# zloshnikrev1.net
KiCad netlist of a schematic drawn in EAGLE
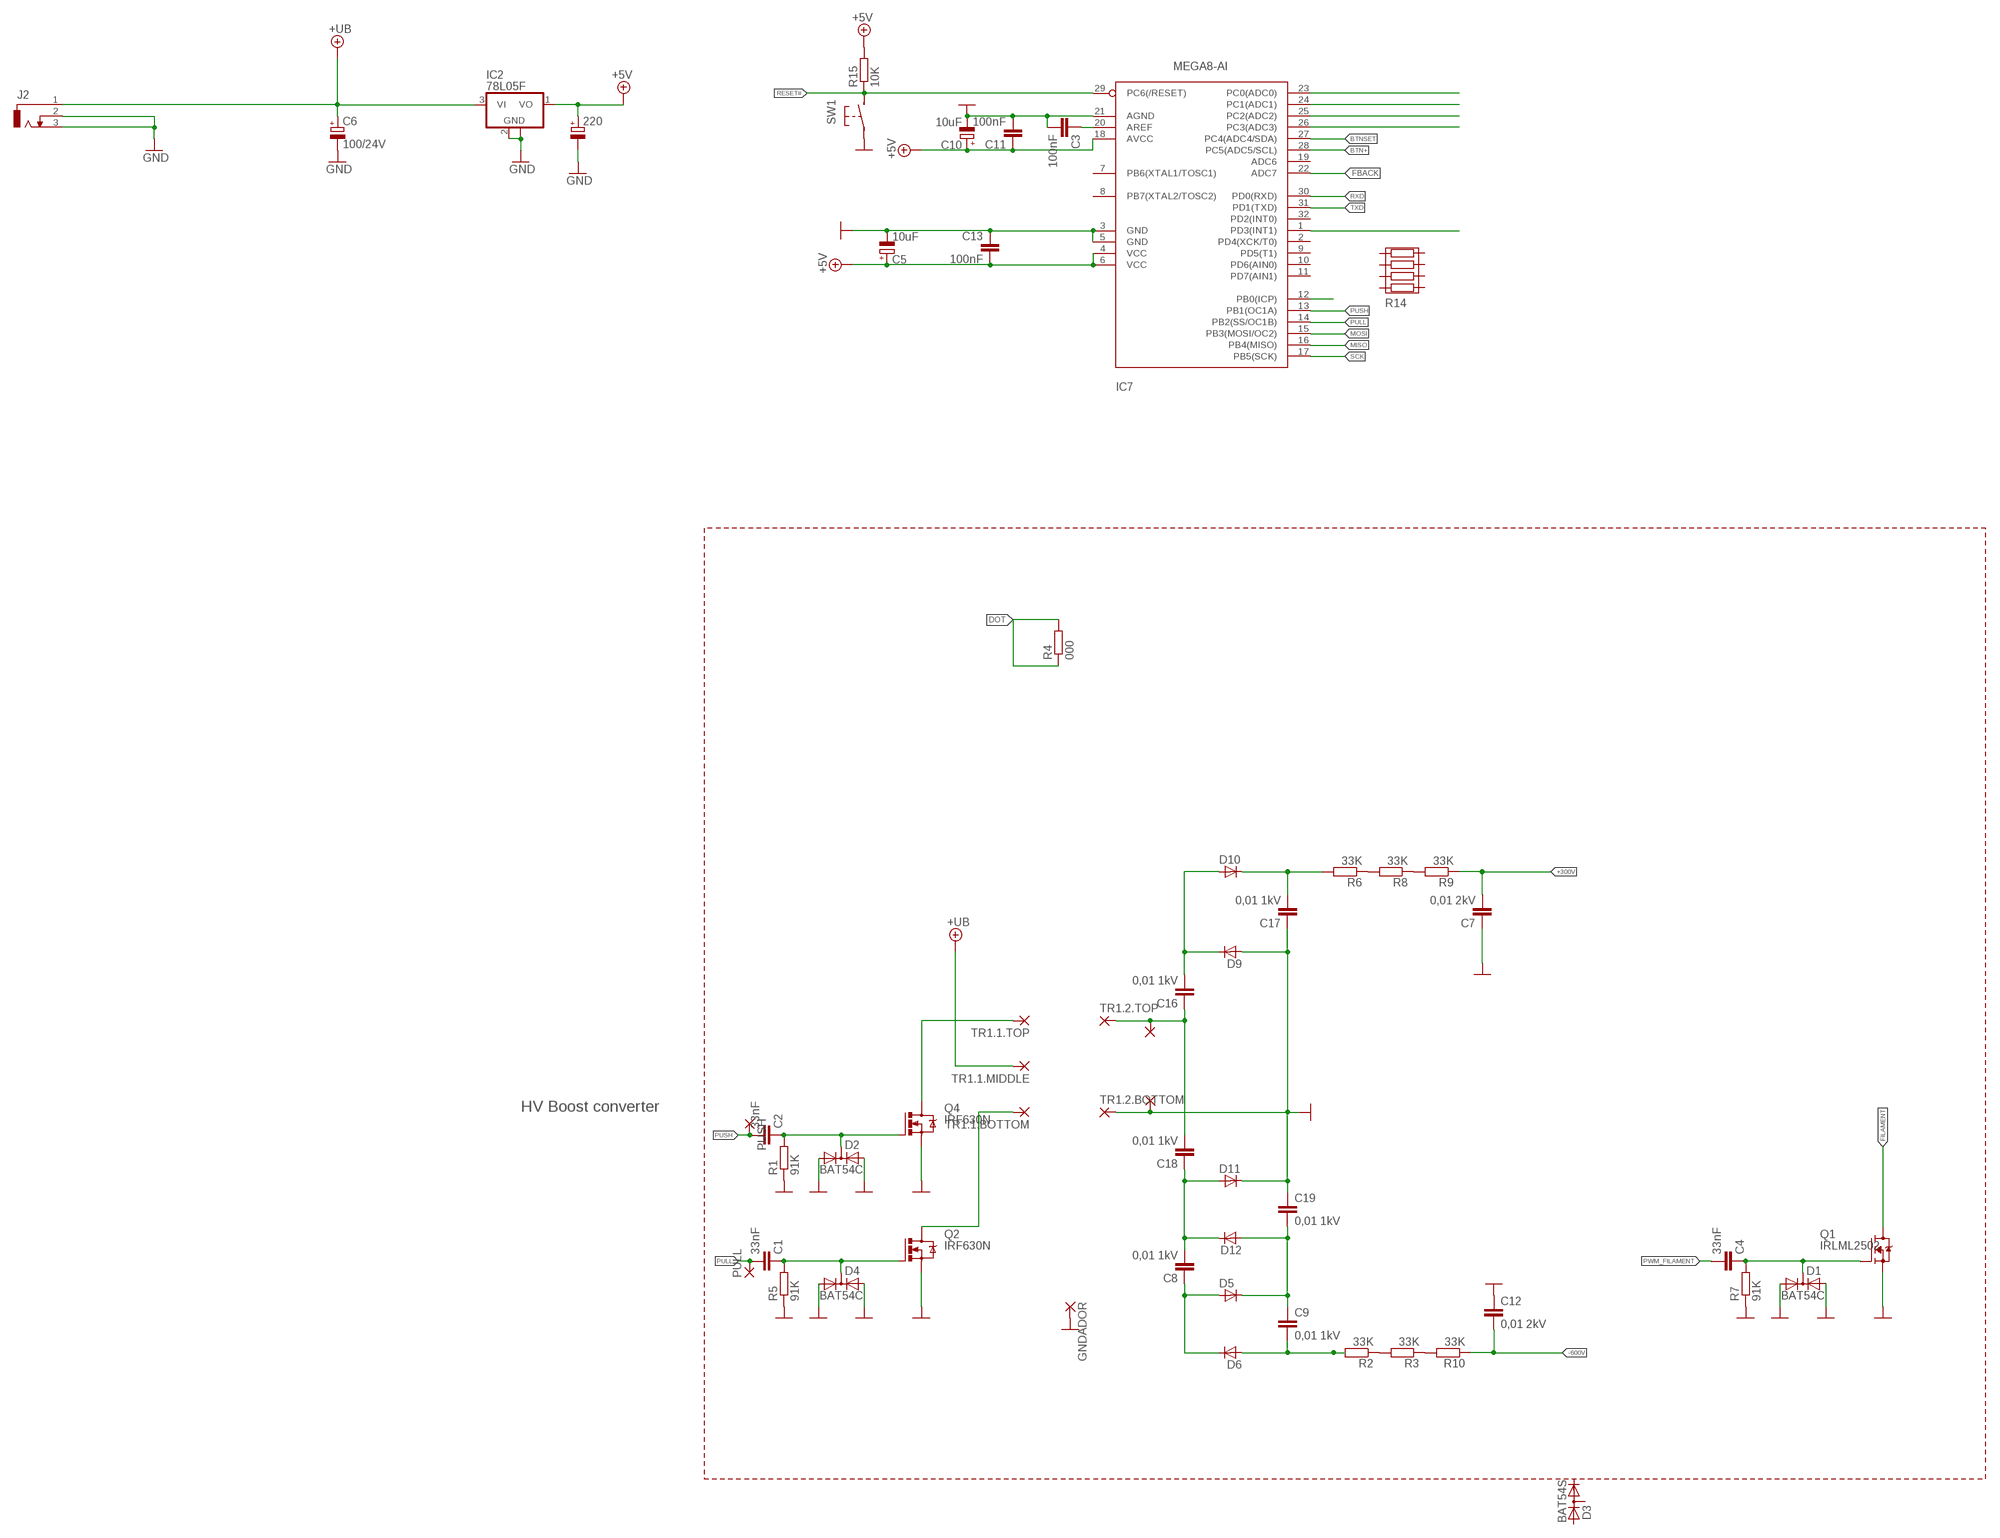
[diagram p0: schematic, sheet 1]

(export (version "E")
  (design (tool "Eeschema 10.0.6"))
  (components
    (comp (ref "220")
      (value "CPOL-EUD/7343-31R")
      (footprint "eagle-import:D_7343-31R")
      (libsource (lib "eagle-import") (part "CPOL-EUD/7343-31R"))
    )
    (comp (ref "C1")
      (value "33nF")
      (footprint "eagle-import:C0805S")
      (libsource (lib "eagle-import") (part "C-EUC0805S"))
    )
    (comp (ref "C2")
      (value "33nF")
      (footprint "eagle-import:C0805S")
      (libsource (lib "eagle-import") (part "C-EUC0805S"))
    )
    (comp (ref "C3")
      (value "100nF")
      (footprint "eagle-import:C0603K")
      (libsource (lib "eagle-import") (part "rcl_C-EUC0603K"))
    )
    (comp (ref "C4")
      (value "33nF")
      (footprint "eagle-import:C0805S")
      (libsource (lib "eagle-import") (part "C-EUC0805S"))
    )
    (comp (ref "C5")
      (value "10uF")
      (footprint "eagle-import:SMC_B")
      (libsource (lib "eagle-import") (part "CPOL-EUSMCB"))
    )
    (comp (ref "C6")
      (value "100/24V")
      (footprint "eagle-import:E3,5-8")
      (libsource (lib "eagle-import") (part "CPOL-EUE3.5-8"))
    )
    (comp (ref "C7")
      (value "0,01 2kV")
      (footprint "eagle-import:C1812")
      (libsource (lib "eagle-import") (part "C-EUC1812"))
    )
    (comp (ref "C8")
      (value "0,01 1kV")
      (footprint "eagle-import:C2220K")
      (libsource (lib "eagle-import") (part "C-EUC2220K"))
    )
    (comp (ref "C9")
      (value "0,01 1kV")
      (footprint "eagle-import:C2220K")
      (libsource (lib "eagle-import") (part "C-EUC2220K"))
    )
    (comp (ref "C10")
      (value "10uF")
      (footprint "eagle-import:SMC_B")
      (libsource (lib "eagle-import") (part "CPOL-EUSMCB"))
    )
    (comp (ref "C11")
      (value "100nF")
      (footprint "eagle-import:C0603K")
      (libsource (lib "eagle-import") (part "rcl_C-EUC0603K"))
    )
    (comp (ref "C12")
      (value "0,01 2kV")
      (footprint "eagle-import:C1812")
      (libsource (lib "eagle-import") (part "C-EUC1812"))
    )
    (comp (ref "C13")
      (value "100nF")
      (footprint "eagle-import:C0603K")
      (libsource (lib "eagle-import") (part "rcl_C-EUC0603K"))
    )
    (comp (ref "C16")
      (value "0,01 1kV")
      (footprint "eagle-import:C2220K")
      (libsource (lib "eagle-import") (part "C-EUC2220K"))
    )
    (comp (ref "C17")
      (value "0,01 1kV")
      (footprint "eagle-import:C2220K")
      (libsource (lib "eagle-import") (part "C-EUC2220K"))
    )
    (comp (ref "C18")
      (value "0,01 1kV")
      (footprint "eagle-import:C2220K")
      (libsource (lib "eagle-import") (part "C-EUC2220K"))
    )
    (comp (ref "C19")
      (value "0,01 1kV")
      (footprint "eagle-import:C2220K")
      (libsource (lib "eagle-import") (part "C-EUC2220K"))
    )
    (comp (ref "D1")
      (value "BAT54C")
      (footprint "eagle-import:SOT23")
      (libsource (lib "eagle-import") (part "DIODE-2AC|CASOT23"))
    )
    (comp (ref "D2")
      (value "BAT54C")
      (footprint "eagle-import:SOT23")
      (libsource (lib "eagle-import") (part "DIODE-2AC|CASOT23"))
    )
    (comp (ref "D3")
      (value "BAT54S")
      (footprint "eagle-import:SOT23@1")
      (libsource (lib "eagle-import") (part "DIODE_2CACA-SOT23"))
    )
    (comp (ref "D4")
      (value "BAT54C")
      (footprint "eagle-import:SOT23")
      (libsource (lib "eagle-import") (part "DIODE-2AC|CASOT23"))
    )
    (comp (ref "D5")
      (value "D-SOD-87")
      (footprint "eagle-import:SOD87")
      (libsource (lib "eagle-import") (part "D-SOD-87"))
    )
    (comp (ref "D6")
      (value "D-SOD-87")
      (footprint "eagle-import:SOD87")
      (libsource (lib "eagle-import") (part "D-SOD-87"))
    )
    (comp (ref "D9")
      (value "D-SOD-87")
      (footprint "eagle-import:SOD87")
      (libsource (lib "eagle-import") (part "D-SOD-87"))
    )
    (comp (ref "D10")
      (value "D-SOD-87")
      (footprint "eagle-import:SOD87")
      (libsource (lib "eagle-import") (part "D-SOD-87"))
    )
    (comp (ref "D11")
      (value "D-SOD-87")
      (footprint "eagle-import:SOD87")
      (libsource (lib "eagle-import") (part "D-SOD-87"))
    )
    (comp (ref "D12")
      (value "D-SOD-87")
      (footprint "eagle-import:SOD87")
      (libsource (lib "eagle-import") (part "D-SOD-87"))
    )
    (comp (ref "GNDADOR")
      (value "1,6/0,8")
      (footprint "eagle-import:1,6_0,8")
      (libsource (lib "eagle-import") (part "1,6/0,8"))
    )
    (comp (ref "IC2")
      (value "78L05F")
      (footprint "eagle-import:SOT89")
      (libsource (lib "eagle-import") (part "78LF05"))
    )
    (comp (ref "IC7")
      (value "MEGA8-AI")
      (footprint "eagle-import:TQFP32-08")
      (libsource (lib "eagle-import") (part "MEGA8-AI"))
    )
    (comp (ref "J2")
      (value "DCJ-SMALL")
      (footprint "eagle-import:DCJ-SMALL")
      (libsource (lib "eagle-import") (part "DCJ-SMALL"))
    )
    (comp (ref "PULL")
      (value "1,6/0,8")
      (footprint "eagle-import:1,6_0,8")
      (libsource (lib "eagle-import") (part "1,6/0,8"))
    )
    (comp (ref "PUSH")
      (value "1,6/0,8")
      (footprint "eagle-import:1,6_0,8")
      (libsource (lib "eagle-import") (part "1,6/0,8"))
    )
    (comp (ref "Q1")
      (value "IRLML2502")
      (footprint "eagle-import:SOT23-3")
      (libsource (lib "eagle-import") (part "IRLML2502"))
    )
    (comp (ref "Q2")
      (value "IRF630N")
      (footprint "eagle-import:TO220BV")
      (libsource (lib "eagle-import") (part "IRF740"))
    )
    (comp (ref "Q4")
      (value "IRF630N")
      (footprint "eagle-import:TO220BV")
      (libsource (lib "eagle-import") (part "IRF740"))
    )
    (comp (ref "R1")
      (value "91K")
      (footprint "eagle-import:R0805-SVO")
      (libsource (lib "eagle-import") (part "R-EU_R0805S"))
    )
    (comp (ref "R2")
      (value "33K")
      (footprint "eagle-import:R0805-SVO")
      (libsource (lib "eagle-import") (part "R-EU_R0805S"))
    )
    (comp (ref "R3")
      (value "33K")
      (footprint "eagle-import:R0805-SVO")
      (libsource (lib "eagle-import") (part "R-EU_R0805S"))
    )
    (comp (ref "R4")
      (value "000")
      (footprint "eagle-import:R0805-SVO")
      (libsource (lib "eagle-import") (part "R-EU_R0805S"))
    )
    (comp (ref "R5")
      (value "91K")
      (footprint "eagle-import:R0805-SVO")
      (libsource (lib "eagle-import") (part "R-EU_R0805S"))
    )
    (comp (ref "R6")
      (value "33K")
      (footprint "eagle-import:R0805-SVO")
      (libsource (lib "eagle-import") (part "R-EU_R0805S"))
    )
    (comp (ref "R7")
      (value "91K")
      (footprint "eagle-import:R0805-SVO")
      (libsource (lib "eagle-import") (part "R-EU_R0805S"))
    )
    (comp (ref "R8")
      (value "33K")
      (footprint "eagle-import:R0805-SVO")
      (libsource (lib "eagle-import") (part "R-EU_R0805S"))
    )
    (comp (ref "R9")
      (value "33K")
      (footprint "eagle-import:R0805-SVO")
      (libsource (lib "eagle-import") (part "R-EU_R0805S"))
    )
    (comp (ref "R10")
      (value "33K")
      (footprint "eagle-import:R0805-SVO")
      (libsource (lib "eagle-import") (part "R-EU_R0805S"))
    )
    (comp (ref "R14")
      (value "RES4")
      (footprint "eagle-import:RESSMD-YC16")
      (libsource (lib "eagle-import") (part "RES4"))
    )
    (comp (ref "R15")
      (value "10K")
      (footprint "eagle-import:R0805-SVO")
      (libsource (lib "eagle-import") (part "R-EU_R0805S"))
    )
    (comp (ref "SW1")
      (value "BUTTON-IT_1181")
      (footprint "eagle-import:SW_IT1181")
      (libsource (lib "eagle-import") (part "BUTTON-IT_1181"))
    )
    (comp (ref "TR1.1.BOTTOM")
      (value "1,6/0,8")
      (footprint "eagle-import:1,6_0,8")
      (libsource (lib "eagle-import") (part "1,6/0,8"))
    )
    (comp (ref "TR1.1.MIDDLE")
      (value "1,6/0,8")
      (footprint "eagle-import:1,6_0,8")
      (libsource (lib "eagle-import") (part "1,6/0,8"))
    )
    (comp (ref "TR1.1.TOP")
      (value "1,6/0,8")
      (footprint "eagle-import:1,6_0,8")
      (libsource (lib "eagle-import") (part "1,6/0,8"))
    )
    (comp (ref "TR1.2.BOTTOM")
      (value "1,6/0,8")
      (footprint "eagle-import:1,6_0,8")
      (libsource (lib "eagle-import") (part "1,6/0,8"))
    )
    (comp (ref "TR1.2.BOTTOM1")
      (value "1,6/0,8")
      (footprint "eagle-import:1,6_0,8")
      (libsource (lib "eagle-import") (part "1,6/0,8"))
    )
    (comp (ref "TR1.2.TOP")
      (value "1,6/0,8")
      (footprint "eagle-import:1,6_0,8")
      (libsource (lib "eagle-import") (part "1,6/0,8"))
    )
    (comp (ref "TR1.2.TOP1")
      (value "1,6/0,8")
      (footprint "eagle-import:1,6_0,8")
      (libsource (lib "eagle-import") (part "1,6/0,8"))
    )
  )
  (nets
    (net (code "1") (name "+5V") (class "Default")
      (node (ref "220") (pin "+") (pinfunction "+_+") (pintype "passive"))
      (node (ref "C10") (pin "+") (pinfunction "+_+") (pintype "passive"))
      (node (ref "C11") (pin "1") (pinfunction "1_1") (pintype "passive"))
      (node (ref "C13") (pin "2") (pinfunction "2_2") (pintype "passive"))
      (node (ref "C5") (pin "+") (pinfunction "+_+") (pintype "passive"))
      (node (ref "IC2") (pin "1") (pinfunction "VO_1") (pintype "passive"))
      (node (ref "IC7") (pin "18") (pinfunction "AVCC_18") (pintype "power_in"))
      (node (ref "IC7") (pin "4") (pinfunction "VCC_4") (pintype "power_in"))
      (node (ref "IC7") (pin "6") (pinfunction "VCC_6") (pintype "power_in"))
      (node (ref "R15") (pin "2") (pinfunction "2_2") (pintype "passive"))
    )
    (net (code "2") (name "+300V") (class "Default")
      (node (ref "C7") (pin "2") (pinfunction "2_2") (pintype "passive"))
      (node (ref "R9") (pin "1") (pinfunction "1_1") (pintype "passive"))
    )
    (net (code "3") (name "+UB") (class "Default")
      (node (ref "C6") (pin "+") (pinfunction "+_+") (pintype "passive"))
      (node (ref "IC2") (pin "3") (pinfunction "VI_3") (pintype "input"))
      (node (ref "J2") (pin "1") (pinfunction "1_1") (pintype "passive"))
      (node (ref "TR1.1.MIDDLE") (pin "1") (pinfunction "P_1") (pintype "passive"))
    )
    (net (code "4") (name "-600V") (class "Default")
      (node (ref "C12") (pin "2") (pinfunction "2_2") (pintype "passive"))
      (node (ref "R10") (pin "1") (pinfunction "1_1") (pintype "passive"))
    )
    (net (code "5") (name "BTN+") (class "Default")
      (node (ref "IC7") (pin "28") (pinfunction "PC5(ADC5/SCL)_28") (pintype "bidirectional"))
    )
    (net (code "6") (name "BTNSET") (class "Default")
      (node (ref "IC7") (pin "27") (pinfunction "PC4(ADC4/SDA)_27") (pintype "bidirectional"))
    )
    (net (code "7") (name "DOT") (class "Default")
      (node (ref "IC7") (pin "1") (pinfunction "PD3(INT1)_1") (pintype "bidirectional"))
      (node (ref "R4") (pin "1") (pinfunction "1_1") (pintype "passive"))
      (node (ref "R4") (pin "2") (pinfunction "2_2") (pintype "passive"))
    )
    (net (code "8") (name "FBACK") (class "Default")
      (node (ref "IC7") (pin "22") (pinfunction "ADC7_22") (pintype "bidirectional"))
    )
    (net (code "9") (name "FILAMENT") (class "Default")
      (node (ref "Q1") (pin "3") (pinfunction "D_3") (pintype "passive"))
    )
    (net (code "10") (name "GND") (class "Default")
      (node (ref "220") (pin "-") (pinfunction "-_-") (pintype "passive"))
      (node (ref "C10") (pin "-") (pinfunction "-_-") (pintype "passive"))
      (node (ref "C11") (pin "2") (pinfunction "2_2") (pintype "passive"))
      (node (ref "C12") (pin "1") (pinfunction "1_1") (pintype "passive"))
      (node (ref "C13") (pin "1") (pinfunction "1_1") (pintype "passive"))
      (node (ref "C17") (pin "1") (pinfunction "1_1") (pintype "passive"))
      (node (ref "C19") (pin "1") (pinfunction "1_1") (pintype "passive"))
      (node (ref "C3") (pin "2") (pinfunction "2_2") (pintype "passive"))
      (node (ref "C5") (pin "-") (pinfunction "-_-") (pintype "passive"))
      (node (ref "C6") (pin "-") (pinfunction "-_-") (pintype "passive"))
      (node (ref "C7") (pin "1") (pinfunction "1_1") (pintype "passive"))
      (node (ref "D1") (pin "1") (pinfunction "A1_1") (pintype "passive"))
      (node (ref "D1") (pin "2") (pinfunction "A2_2") (pintype "passive"))
      (node (ref "D11") (pin "1") (pinfunction "C_1") (pintype "passive"))
      (node (ref "D2") (pin "1") (pinfunction "A1_1") (pintype "passive"))
      (node (ref "D2") (pin "2") (pinfunction "A2_2") (pintype "passive"))
      (node (ref "D4") (pin "1") (pinfunction "A1_1") (pintype "passive"))
      (node (ref "D4") (pin "2") (pinfunction "A2_2") (pintype "passive"))
      (node (ref "D9") (pin "2") (pinfunction "A_2") (pintype "passive"))
      (node (ref "GNDADOR") (pin "1") (pinfunction "P_1") (pintype "passive"))
      (node (ref "IC2") (pin "2") (pinfunction "GND_2") (pintype "passive"))
      (node (ref "IC2") (pin "2@1") (pinfunction "GND_2@1") (pintype "passive"))
      (node (ref "IC7") (pin "21") (pinfunction "AGND_21") (pintype "power_in"))
      (node (ref "IC7") (pin "3") (pinfunction "GND_3") (pintype "power_in"))
      (node (ref "IC7") (pin "5") (pinfunction "GND_5") (pintype "power_in"))
      (node (ref "J2") (pin "2") (pinfunction "2_2") (pintype "passive"))
      (node (ref "J2") (pin "3") (pinfunction "3_3") (pintype "passive"))
      (node (ref "Q1") (pin "2") (pinfunction "S_2") (pintype "passive"))
      (node (ref "Q2") (pin "S") (pinfunction "S_S") (pintype "passive"))
      (node (ref "Q4") (pin "S") (pinfunction "S_S") (pintype "passive"))
      (node (ref "R1") (pin "1") (pinfunction "1_1") (pintype "passive"))
      (node (ref "R5") (pin "1") (pinfunction "1_1") (pintype "passive"))
      (node (ref "R7") (pin "1") (pinfunction "1_1") (pintype "passive"))
      (node (ref "SW1") (pin "P$1") (pinfunction "P1_P$1") (pintype "passive"))
      (node (ref "TR1.2.BOTTOM") (pin "1") (pinfunction "P_1") (pintype "passive"))
      (node (ref "TR1.2.BOTTOM1") (pin "1") (pinfunction "P_1") (pintype "passive"))
    )
    (net (code "11") (name "MISO") (class "Default")
      (node (ref "IC7") (pin "16") (pinfunction "PB4(MISO)_16") (pintype "bidirectional"))
    )
    (net (code "12") (name "MOSI") (class "Default")
      (node (ref "IC7") (pin "15") (pinfunction "PB3(MOSI/OC2)_15") (pintype "bidirectional"))
    )
    (net (code "13") (name "Net-(D1-C)") (class "Default")
      (node (ref "C4") (pin "1") (pinfunction "1_1") (pintype "passive"))
      (node (ref "D1") (pin "3") (pinfunction "C_3") (pintype "passive"))
      (node (ref "Q1") (pin "1") (pinfunction "G_1") (pintype "passive"))
      (node (ref "R7") (pin "2") (pinfunction "2_2") (pintype "passive"))
    )
    (net (code "14") (name "Net-(D2-C)") (class "Default")
      (node (ref "C2") (pin "1") (pinfunction "1_1") (pintype "passive"))
      (node (ref "D2") (pin "3") (pinfunction "C_3") (pintype "passive"))
      (node (ref "Q4") (pin "G") (pinfunction "G_G") (pintype "passive"))
      (node (ref "R1") (pin "2") (pinfunction "2_2") (pintype "passive"))
    )
    (net (code "15") (name "Net-(D4-C)") (class "Default")
      (node (ref "C1") (pin "1") (pinfunction "1_1") (pintype "passive"))
      (node (ref "D4") (pin "3") (pinfunction "C_3") (pintype "passive"))
      (node (ref "Q2") (pin "G") (pinfunction "G_G") (pintype "passive"))
      (node (ref "R5") (pin "2") (pinfunction "2_2") (pintype "passive"))
    )
    (net (code "16") (name "Net-(D5-A)") (class "Default")
      (node (ref "C8") (pin "1") (pinfunction "1_1") (pintype "passive"))
      (node (ref "D5") (pin "2") (pinfunction "A_2") (pintype "passive"))
      (node (ref "D6") (pin "1") (pinfunction "C_1") (pintype "passive"))
    )
    (net (code "17") (name "Net-(D6-A)") (class "Default")
      (node (ref "C9") (pin "2") (pinfunction "2_2") (pintype "passive"))
      (node (ref "D6") (pin "2") (pinfunction "A_2") (pintype "passive"))
      (node (ref "R2") (pin "2") (pinfunction "2_2") (pintype "passive"))
    )
    (net (code "18") (name "Net-(D10-A)") (class "Default")
      (node (ref "C16") (pin "2") (pinfunction "2_2") (pintype "passive"))
      (node (ref "D10") (pin "2") (pinfunction "A_2") (pintype "passive"))
      (node (ref "D9") (pin "1") (pinfunction "C_1") (pintype "passive"))
    )
    (net (code "19") (name "Net-(D10-C)") (class "Default")
      (node (ref "C17") (pin "2") (pinfunction "2_2") (pintype "passive"))
      (node (ref "D10") (pin "1") (pinfunction "C_1") (pintype "passive"))
      (node (ref "R6") (pin "2") (pinfunction "2_2") (pintype "passive"))
    )
    (net (code "20") (name "Net-(D11-A)") (class "Default")
      (node (ref "C18") (pin "1") (pinfunction "1_1") (pintype "passive"))
      (node (ref "C8") (pin "2") (pinfunction "2_2") (pintype "passive"))
      (node (ref "D11") (pin "2") (pinfunction "A_2") (pintype "passive"))
      (node (ref "D12") (pin "1") (pinfunction "C_1") (pintype "passive"))
    )
    (net (code "21") (name "Net-(D12-A)") (class "Default")
      (node (ref "C19") (pin "2") (pinfunction "2_2") (pintype "passive"))
      (node (ref "C9") (pin "1") (pinfunction "1_1") (pintype "passive"))
      (node (ref "D12") (pin "2") (pinfunction "A_2") (pintype "passive"))
      (node (ref "D5") (pin "1") (pinfunction "C_1") (pintype "passive"))
    )
    (net (code "22") (name "Net-(IC7-AREF)") (class "Default")
      (node (ref "C3") (pin "1") (pinfunction "1_1") (pintype "passive"))
      (node (ref "IC7") (pin "20") (pinfunction "AREF_20") (pintype "passive"))
    )
    (net (code "23") (name "Net-(R2-Pad1)") (class "Default")
      (node (ref "R2") (pin "1") (pinfunction "1_1") (pintype "passive"))
      (node (ref "R3") (pin "2") (pinfunction "2_2") (pintype "passive"))
    )
    (net (code "24") (name "Net-(R6-Pad1)") (class "Default")
      (node (ref "R6") (pin "1") (pinfunction "1_1") (pintype "passive"))
      (node (ref "R8") (pin "2") (pinfunction "2_2") (pintype "passive"))
    )
    (net (code "25") (name "Net-(R8-Pad1)") (class "Default")
      (node (ref "R8") (pin "1") (pinfunction "1_1") (pintype "passive"))
      (node (ref "R9") (pin "2") (pinfunction "2_2") (pintype "passive"))
    )
    (net (code "26") (name "Net-(R10-Pad2)") (class "Default")
      (node (ref "R10") (pin "2") (pinfunction "2_2") (pintype "passive"))
      (node (ref "R3") (pin "1") (pinfunction "1_1") (pintype "passive"))
    )
    (net (code "27") (name "Net-(TR1.1.BOTTOM-P)") (class "Default")
      (node (ref "Q2") (pin "D") (pinfunction "D_D") (pintype "passive"))
      (node (ref "TR1.1.BOTTOM") (pin "1") (pinfunction "P_1") (pintype "passive"))
    )
    (net (code "28") (name "Net-(TR1.1.TOP-P)") (class "Default")
      (node (ref "Q4") (pin "D") (pinfunction "D_D") (pintype "passive"))
      (node (ref "TR1.1.TOP") (pin "1") (pinfunction "P_1") (pintype "passive"))
    )
    (net (code "29") (name "Net-(TR1.2.TOP-P)") (class "Default")
      (node (ref "C16") (pin "1") (pinfunction "1_1") (pintype "passive"))
      (node (ref "C18") (pin "2") (pinfunction "2_2") (pintype "passive"))
      (node (ref "TR1.2.TOP") (pin "1") (pinfunction "P_1") (pintype "passive"))
      (node (ref "TR1.2.TOP1") (pin "1") (pinfunction "P_1") (pintype "passive"))
    )
    (net (code "30") (name "PULL") (class "Default")
      (node (ref "C1") (pin "2") (pinfunction "2_2") (pintype "passive"))
      (node (ref "IC7") (pin "14") (pinfunction "PB2(SS/OC1B)_14") (pintype "bidirectional"))
      (node (ref "PULL") (pin "1") (pinfunction "P_1") (pintype "passive"))
    )
    (net (code "31") (name "PUSH") (class "Default")
      (node (ref "C2") (pin "2") (pinfunction "2_2") (pintype "passive"))
      (node (ref "IC7") (pin "13") (pinfunction "PB1(OC1A)_13") (pintype "bidirectional"))
      (node (ref "PUSH") (pin "1") (pinfunction "P_1") (pintype "passive"))
    )
    (net (code "32") (name "PWM_FILAMENT") (class "Default")
      (node (ref "C4") (pin "2") (pinfunction "2_2") (pintype "passive"))
    )
    (net (code "33") (name "RESET#") (class "Default")
      (node (ref "IC7") (pin "29") (pinfunction "PC6(/RESET)_29") (pintype "bidirectional"))
      (node (ref "R15") (pin "1") (pinfunction "1_1") (pintype "passive"))
      (node (ref "SW1") (pin "P$2") (pinfunction "P2_P$2") (pintype "passive"))
    )
    (net (code "34") (name "RXD") (class "Default")
      (node (ref "IC7") (pin "30") (pinfunction "PD0(RXD)_30") (pintype "bidirectional"))
    )
    (net (code "35") (name "SCK") (class "Default")
      (node (ref "IC7") (pin "17") (pinfunction "PB5(SCK)_17") (pintype "bidirectional"))
    )
    (net (code "36") (name "TXD") (class "Default")
      (node (ref "IC7") (pin "31") (pinfunction "PD1(TXD)_31") (pintype "bidirectional"))
    )
    (net (code "37") (name "unconnected-(D3-A-Pad1)") (class "Default")
      (node (ref "D3") (pin "1") (pinfunction "A_1") (pintype "passive"))
    )
    (net (code "38") (name "unconnected-(D3-AC-Pad3)") (class "Default")
      (node (ref "D3") (pin "3") (pinfunction "AC_3") (pintype "passive"))
    )
    (net (code "39") (name "unconnected-(D3-C-Pad2)") (class "Default")
      (node (ref "D3") (pin "2") (pinfunction "C_2") (pintype "passive"))
    )
    (net (code "40") (name "unconnected-(IC7-ADC6-Pad19)") (class "Default")
      (node (ref "IC7") (pin "19") (pinfunction "ADC6_19") (pintype "bidirectional"))
    )
    (net (code "41") (name "unconnected-(IC7-PB0(ICP)-Pad12)") (class "Default")
      (node (ref "IC7") (pin "12") (pinfunction "PB0(ICP)_12") (pintype "bidirectional"))
    )
    (net (code "42") (name "unconnected-(IC7-PB6(XTAL1{slash}TOSC1)-Pad7)") (class "Default")
      (node (ref "IC7") (pin "7") (pinfunction "PB6(XTAL1/TOSC1)_7") (pintype "bidirectional"))
    )
    (net (code "43") (name "unconnected-(IC7-PB7(XTAL2{slash}TOSC2)-Pad8)") (class "Default")
      (node (ref "IC7") (pin "8") (pinfunction "PB7(XTAL2/TOSC2)_8") (pintype "bidirectional"))
    )
    (net (code "44") (name "unconnected-(IC7-PC0(ADC0)-Pad23)") (class "Default")
      (node (ref "IC7") (pin "23") (pinfunction "PC0(ADC0)_23") (pintype "bidirectional"))
    )
    (net (code "45") (name "unconnected-(IC7-PC1(ADC1)-Pad24)") (class "Default")
      (node (ref "IC7") (pin "24") (pinfunction "PC1(ADC1)_24") (pintype "bidirectional"))
    )
    (net (code "46") (name "unconnected-(IC7-PC2(ADC2)-Pad25)") (class "Default")
      (node (ref "IC7") (pin "25") (pinfunction "PC2(ADC2)_25") (pintype "bidirectional"))
    )
    (net (code "47") (name "unconnected-(IC7-PC3(ADC3)-Pad26)") (class "Default")
      (node (ref "IC7") (pin "26") (pinfunction "PC3(ADC3)_26") (pintype "bidirectional"))
    )
    (net (code "48") (name "unconnected-(IC7-PD2(INT0)-Pad32)") (class "Default")
      (node (ref "IC7") (pin "32") (pinfunction "PD2(INT0)_32") (pintype "bidirectional"))
    )
    (net (code "49") (name "unconnected-(IC7-PD4(XCK{slash}T0)-Pad2)") (class "Default")
      (node (ref "IC7") (pin "2") (pinfunction "PD4(XCK/T0)_2") (pintype "bidirectional"))
    )
    (net (code "50") (name "unconnected-(IC7-PD5(T1)-Pad9)") (class "Default")
      (node (ref "IC7") (pin "9") (pinfunction "PD5(T1)_9") (pintype "bidirectional"))
    )
    (net (code "51") (name "unconnected-(IC7-PD6(AIN0)-Pad10)") (class "Default")
      (node (ref "IC7") (pin "10") (pinfunction "PD6(AIN0)_10") (pintype "bidirectional"))
    )
    (net (code "52") (name "unconnected-(IC7-PD7(AIN1)-Pad11)") (class "Default")
      (node (ref "IC7") (pin "11") (pinfunction "PD7(AIN1)_11") (pintype "bidirectional"))
    )
    (net (code "53") (name "unconnected-(R14-1.1-PadR1$1)") (class "Default")
      (node (ref "R14") (pin "R1$1") (pinfunction "1.1_R1$1") (pintype "passive"))
    )
    (net (code "54") (name "unconnected-(R14-1.2-PadR1$2)") (class "Default")
      (node (ref "R14") (pin "R1$2") (pinfunction "1.2_R1$2") (pintype "passive"))
    )
    (net (code "55") (name "unconnected-(R14-2.1-PadR2$1)") (class "Default")
      (node (ref "R14") (pin "R2$1") (pinfunction "2.1_R2$1") (pintype "passive"))
    )
    (net (code "56") (name "unconnected-(R14-2.2-PadR2$2)") (class "Default")
      (node (ref "R14") (pin "R2$2") (pinfunction "2.2_R2$2") (pintype "passive"))
    )
    (net (code "57") (name "unconnected-(R14-3.1-PadR3$1)") (class "Default")
      (node (ref "R14") (pin "R3$1") (pinfunction "3.1_R3$1") (pintype "passive"))
    )
    (net (code "58") (name "unconnected-(R14-3.2-PadR3$2)") (class "Default")
      (node (ref "R14") (pin "R3$2") (pinfunction "3.2_R3$2") (pintype "passive"))
    )
    (net (code "59") (name "unconnected-(R14-4.1-PadR4$1)") (class "Default")
      (node (ref "R14") (pin "R4$1") (pinfunction "4.1_R4$1") (pintype "passive"))
    )
    (net (code "60") (name "unconnected-(R14-4.2-PadR4$2)") (class "Default")
      (node (ref "R14") (pin "R4$2") (pinfunction "4.2_R4$2") (pintype "passive"))
    )
  )
)
